# Tray_1_Expansion_Board_Prototype.net
KiCad netlist of a schematic drawn in Altium Designer
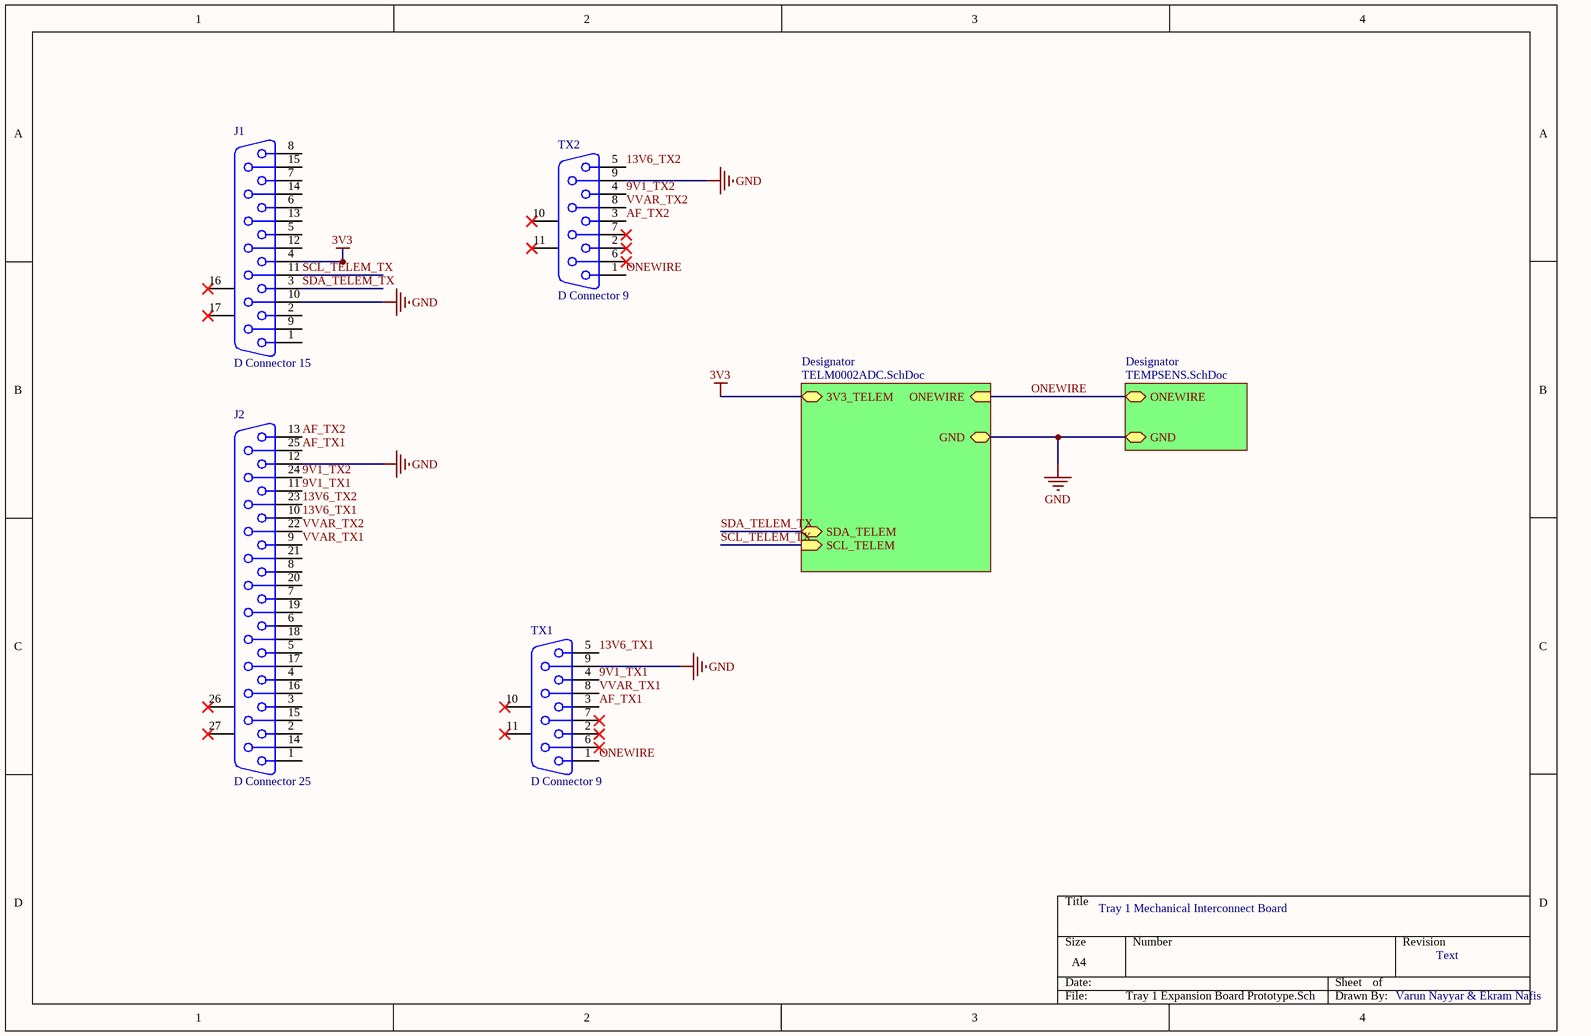
[diagram p0: Tray 1 Expansion Board Prototype.SchDoc]

(export (version "E")
  (design (tool "Eeschema 10.0.6"))
  (components
    (comp (ref "J1")
      (value "D Connector 15")
      (footprint "DSUB1.385-2H15")
      (description "Receptacle Assembly, 15 Position, Right Angle")
      (libsource (lib "Tray 1 Expansion Board Prototype") (part "D Connector 15"))
    )
    (comp (ref "J2")
      (value "D Connector 25")
      (footprint "DSUB1.385-2H25A")
      (description "Receptacle Assembly, 25 Position, Right Angle")
      (libsource (lib "Tray 1 Expansion Board Prototype") (part "D Connector 25"))
    )
    (comp (ref "TX1")
      (value "D Connector 9")
      (footprint "DSUB Upright")
      (description "Receptacle Assembly, 9 Position, Right Angle")
      (libsource (lib "Tray 1 Expansion Board Prototype") (part "D Connector 9"))
    )
    (comp (ref "TX2")
      (value "D Connector 9")
      (footprint "DSUB Upright")
      (description "Receptacle Assembly, 9 Position, Right Angle")
      (libsource (lib "Tray 1 Expansion Board Prototype") (part "D Connector 9"))
    )
  )
  (nets
    (net (code "1") (name "/9V1_TX1") (class "Default")
      (node (ref "J2") (pin "11") (pinfunction "11_11") (pintype "passive"))
      (node (ref "TX1") (pin "4") (pinfunction "4_4") (pintype "passive"))
    )
    (net (code "2") (name "/9V1_TX2") (class "Default")
      (node (ref "J2") (pin "24") (pinfunction "24_24") (pintype "passive"))
      (node (ref "TX2") (pin "4") (pinfunction "4_4") (pintype "passive"))
    )
    (net (code "3") (name "/13V6_TX1") (class "Default")
      (node (ref "J2") (pin "10") (pinfunction "10_10") (pintype "passive"))
      (node (ref "TX1") (pin "5") (pinfunction "5_5") (pintype "passive"))
    )
    (net (code "4") (name "/13V6_TX2") (class "Default")
      (node (ref "J2") (pin "23") (pinfunction "23_23") (pintype "passive"))
      (node (ref "TX2") (pin "5") (pinfunction "5_5") (pintype "passive"))
    )
    (net (code "5") (name "/AF_TX1") (class "Default")
      (node (ref "J2") (pin "25") (pinfunction "25_25") (pintype "passive"))
      (node (ref "TX1") (pin "3") (pinfunction "3_3") (pintype "passive"))
    )
    (net (code "6") (name "/AF_TX2") (class "Default")
      (node (ref "J2") (pin "13") (pinfunction "13_13") (pintype "passive"))
      (node (ref "TX2") (pin "3") (pinfunction "3_3") (pintype "passive"))
    )
    (net (code "7") (name "/ONEWIRE") (class "Default")
      (node (ref "TX1") (pin "1") (pinfunction "1_1") (pintype "passive"))
      (node (ref "TX2") (pin "1") (pinfunction "1_1") (pintype "passive"))
    )
    (net (code "8") (name "/SCL_TELEM_TX") (class "Default")
      (node (ref "J1") (pin "11") (pinfunction "11_11") (pintype "passive"))
    )
    (net (code "9") (name "/SDA_TELEM_TX") (class "Default")
      (node (ref "J1") (pin "3") (pinfunction "3_3") (pintype "passive"))
    )
    (net (code "10") (name "/VVAR_TX1") (class "Default")
      (node (ref "J2") (pin "9") (pinfunction "9_9") (pintype "passive"))
      (node (ref "TX1") (pin "8") (pinfunction "8_8") (pintype "passive"))
    )
    (net (code "11") (name "/VVAR_TX2") (class "Default")
      (node (ref "J2") (pin "22") (pinfunction "22_22") (pintype "passive"))
      (node (ref "TX2") (pin "8") (pinfunction "8_8") (pintype "passive"))
    )
    (net (code "12") (name "3V3") (class "Default")
      (node (ref "J1") (pin "4") (pinfunction "4_4") (pintype "passive"))
    )
    (net (code "13") (name "GND") (class "Default")
      (node (ref "J1") (pin "10") (pinfunction "10_10") (pintype "passive"))
      (node (ref "J2") (pin "12") (pinfunction "12_12") (pintype "passive"))
      (node (ref "TX1") (pin "9") (pinfunction "9_9") (pintype "passive"))
      (node (ref "TX2") (pin "9") (pinfunction "9_9") (pintype "passive"))
    )
    (net (code "14") (name "unconnected-(J1-MH1-Pad16)") (class "Default")
      (node (ref "J1") (pin "16") (pinfunction "MH1_16") (pintype "passive+no_connect"))
    )
    (net (code "15") (name "unconnected-(J1-MH2-Pad17)") (class "Default")
      (node (ref "J1") (pin "17") (pinfunction "MH2_17") (pintype "passive+no_connect"))
    )
    (net (code "16") (name "unconnected-(J1-Pad1)") (class "Default")
      (node (ref "J1") (pin "1") (pinfunction "1_1") (pintype "passive"))
    )
    (net (code "17") (name "unconnected-(J1-Pad2)") (class "Default")
      (node (ref "J1") (pin "2") (pinfunction "2_2") (pintype "passive"))
    )
    (net (code "18") (name "unconnected-(J1-Pad5)") (class "Default")
      (node (ref "J1") (pin "5") (pinfunction "5_5") (pintype "passive"))
    )
    (net (code "19") (name "unconnected-(J1-Pad6)") (class "Default")
      (node (ref "J1") (pin "6") (pinfunction "6_6") (pintype "passive"))
    )
    (net (code "20") (name "unconnected-(J1-Pad7)") (class "Default")
      (node (ref "J1") (pin "7") (pinfunction "7_7") (pintype "passive"))
    )
    (net (code "21") (name "unconnected-(J1-Pad8)") (class "Default")
      (node (ref "J1") (pin "8") (pinfunction "8_8") (pintype "passive"))
    )
    (net (code "22") (name "unconnected-(J1-Pad9)") (class "Default")
      (node (ref "J1") (pin "9") (pinfunction "9_9") (pintype "passive"))
    )
    (net (code "23") (name "unconnected-(J1-Pad12)") (class "Default")
      (node (ref "J1") (pin "12") (pinfunction "12_12") (pintype "passive"))
    )
    (net (code "24") (name "unconnected-(J1-Pad13)") (class "Default")
      (node (ref "J1") (pin "13") (pinfunction "13_13") (pintype "passive"))
    )
    (net (code "25") (name "unconnected-(J1-Pad14)") (class "Default")
      (node (ref "J1") (pin "14") (pinfunction "14_14") (pintype "passive"))
    )
    (net (code "26") (name "unconnected-(J1-Pad15)") (class "Default")
      (node (ref "J1") (pin "15") (pinfunction "15_15") (pintype "passive"))
    )
    (net (code "27") (name "unconnected-(J2-MH1-Pad26)") (class "Default")
      (node (ref "J2") (pin "26") (pinfunction "MH1_26") (pintype "passive+no_connect"))
    )
    (net (code "28") (name "unconnected-(J2-MH2-Pad27)") (class "Default")
      (node (ref "J2") (pin "27") (pinfunction "MH2_27") (pintype "passive+no_connect"))
    )
    (net (code "29") (name "unconnected-(J2-Pad1)") (class "Default")
      (node (ref "J2") (pin "1") (pinfunction "1_1") (pintype "passive"))
    )
    (net (code "30") (name "unconnected-(J2-Pad2)") (class "Default")
      (node (ref "J2") (pin "2") (pinfunction "2_2") (pintype "passive"))
    )
    (net (code "31") (name "unconnected-(J2-Pad3)") (class "Default")
      (node (ref "J2") (pin "3") (pinfunction "3_3") (pintype "passive"))
    )
    (net (code "32") (name "unconnected-(J2-Pad4)") (class "Default")
      (node (ref "J2") (pin "4") (pinfunction "4_4") (pintype "passive"))
    )
    (net (code "33") (name "unconnected-(J2-Pad5)") (class "Default")
      (node (ref "J2") (pin "5") (pinfunction "5_5") (pintype "passive"))
    )
    (net (code "34") (name "unconnected-(J2-Pad6)") (class "Default")
      (node (ref "J2") (pin "6") (pinfunction "6_6") (pintype "passive"))
    )
    (net (code "35") (name "unconnected-(J2-Pad7)") (class "Default")
      (node (ref "J2") (pin "7") (pinfunction "7_7") (pintype "passive"))
    )
    (net (code "36") (name "unconnected-(J2-Pad8)") (class "Default")
      (node (ref "J2") (pin "8") (pinfunction "8_8") (pintype "passive"))
    )
    (net (code "37") (name "unconnected-(J2-Pad14)") (class "Default")
      (node (ref "J2") (pin "14") (pinfunction "14_14") (pintype "passive"))
    )
    (net (code "38") (name "unconnected-(J2-Pad15)") (class "Default")
      (node (ref "J2") (pin "15") (pinfunction "15_15") (pintype "passive"))
    )
    (net (code "39") (name "unconnected-(J2-Pad16)") (class "Default")
      (node (ref "J2") (pin "16") (pinfunction "16_16") (pintype "passive"))
    )
    (net (code "40") (name "unconnected-(J2-Pad17)") (class "Default")
      (node (ref "J2") (pin "17") (pinfunction "17_17") (pintype "passive"))
    )
    (net (code "41") (name "unconnected-(J2-Pad18)") (class "Default")
      (node (ref "J2") (pin "18") (pinfunction "18_18") (pintype "passive"))
    )
    (net (code "42") (name "unconnected-(J2-Pad19)") (class "Default")
      (node (ref "J2") (pin "19") (pinfunction "19_19") (pintype "passive"))
    )
    (net (code "43") (name "unconnected-(J2-Pad20)") (class "Default")
      (node (ref "J2") (pin "20") (pinfunction "20_20") (pintype "passive"))
    )
    (net (code "44") (name "unconnected-(J2-Pad21)") (class "Default")
      (node (ref "J2") (pin "21") (pinfunction "21_21") (pintype "passive"))
    )
    (net (code "45") (name "unconnected-(TX1-MH1-Pad10)") (class "Default")
      (node (ref "TX1") (pin "10") (pinfunction "MH1_10") (pintype "passive+no_connect"))
    )
    (net (code "46") (name "unconnected-(TX1-MH2-Pad11)") (class "Default")
      (node (ref "TX1") (pin "11") (pinfunction "MH2_11") (pintype "passive+no_connect"))
    )
    (net (code "47") (name "unconnected-(TX1-Pad2)") (class "Default")
      (node (ref "TX1") (pin "2") (pinfunction "2_2") (pintype "passive+no_connect"))
    )
    (net (code "48") (name "unconnected-(TX1-Pad6)") (class "Default")
      (node (ref "TX1") (pin "6") (pinfunction "6_6") (pintype "passive+no_connect"))
    )
    (net (code "49") (name "unconnected-(TX1-Pad7)") (class "Default")
      (node (ref "TX1") (pin "7") (pinfunction "7_7") (pintype "passive+no_connect"))
    )
    (net (code "50") (name "unconnected-(TX2-MH1-Pad10)") (class "Default")
      (node (ref "TX2") (pin "10") (pinfunction "MH1_10") (pintype "passive+no_connect"))
    )
    (net (code "51") (name "unconnected-(TX2-MH2-Pad11)") (class "Default")
      (node (ref "TX2") (pin "11") (pinfunction "MH2_11") (pintype "passive+no_connect"))
    )
    (net (code "52") (name "unconnected-(TX2-Pad2)") (class "Default")
      (node (ref "TX2") (pin "2") (pinfunction "2_2") (pintype "passive+no_connect"))
    )
    (net (code "53") (name "unconnected-(TX2-Pad6)") (class "Default")
      (node (ref "TX2") (pin "6") (pinfunction "6_6") (pintype "passive+no_connect"))
    )
    (net (code "54") (name "unconnected-(TX2-Pad7)") (class "Default")
      (node (ref "TX2") (pin "7") (pinfunction "7_7") (pintype "passive+no_connect"))
    )
  )
)
